# RF_Antenna.net
KiCad netlist of a schematic drawn in Altium Designer
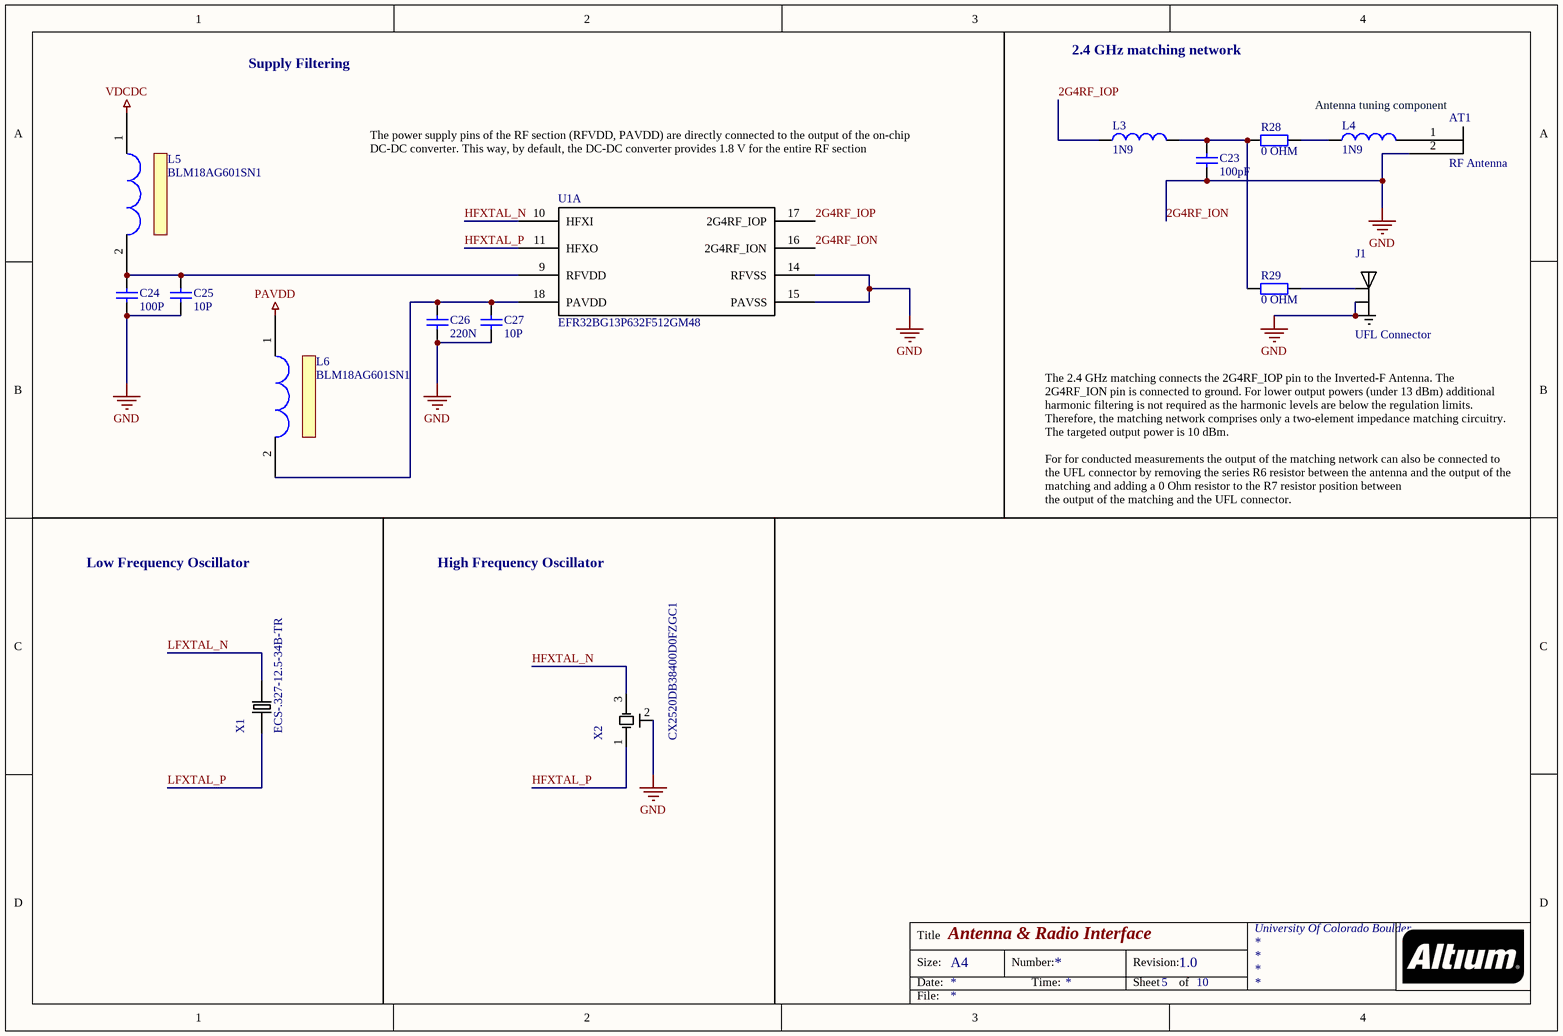
[diagram p0: RF_Antenna.SchDoc]

(export (version "E")
  (design (tool "Eeschema 10.0.6"))
  (components
    (comp (ref "AT1")
      (value "RF Antenna")
      (footprint "PCBComponent_1")
      (libsource (lib "Inverted_F") (part "RF Antenna"))
    )
    (comp (ref "C23")
      (value "100pF")
      (footprint "C1206")
      (description "CAP CER 1.5PF 50V C0G/NP0 0402")
      (fields
        (field (name "MANUFACTURER") "Murata Electronics")
        (field (name "MANUFACTURER PART NUMBER") "GJM1555C1H1R5WB01D")
      )
      (libsource (lib "Miscellaneous Devices") (part "Cap Semi"))
    )
    (comp (ref "C24")
      (value "100P")
      (footprint "1608[0603]")
      (description "CAP CER 100PF 16V X7R 0603")
      (fields
        (field (name "DIGIKEY PART NUMBER") "478-6207-1-ND")
        (field (name "MANUFACTURER") "AVX Corporation")
      )
      (libsource (lib "Miscellaneous Devices") (part "Cap"))
    )
    (comp (ref "C25")
      (value "10P")
      (footprint "1608[0603]")
      (description "CAP CER 10PF 50V C0G/NPO 0603")
      (fields (field (name "DIGI-KEY PART NUMBER") "311-1058-1-ND") (field (name "MANUFACTURER") "Yageo"))
      (libsource (lib "Miscellaneous Devices") (part "Cap"))
    )
    (comp (ref "C26")
      (value "220N")
      (footprint "1608[0603]")
      (description "Capacitor")
      (fields
        (field (name "DIGI-KEY PART NUMBER") "587-1249-1-ND")
        (field (name "MANUFACTURER") "Taiyo Yuden")
      )
      (libsource (lib "Miscellaneous Devices") (part "Cap"))
    )
    (comp (ref "C27")
      (value "10P")
      (footprint "1608[0603]")
      (description "CAP CER 10PF 50V C0G/NPO 0603")
      (fields (field (name "DIGI-KEY PART NUMBER") "311-1058-1-ND") (field (name "MANUFACTURER") "Yageo"))
      (libsource (lib "Miscellaneous Devices") (part "Cap"))
    )
    (comp (ref "J1")
      (value "UFL Connector")
      (footprint "*HRS_U.FL-R-SMT-1(10)")
      (description "U.FL Series 6 Ghz 50 Ohm Ultra-small SMT Coaxial Cable Receptacle")
      (fields
        (field (name "MOUSER PART NUMBER") "798-U.FL-R-SMT-110")
        (field (name "MANUFACTURER PART NUMBER") "U.FL-R-SMT-1(10)")
      )
      (libsource (lib "U.FL-R-SMT-1_10_") (part "U.FL-R-SMT-1(10)"))
    )
    (comp (ref "L3")
      (value "1N9")
      (footprint "0402-A")
      (description "FIXED IND 1.9NH 220MA 300 MOHM")
      (fields
        (field (name "MOUSER PART NUMBER") "81-LQP15MN1N9W02D")
        (field (name "MANUFACTURER") "Murata Electronics")
      )
      (libsource (lib "Miscellaneous Devices") (part "Inductor"))
    )
    (comp (ref "L4")
      (value "1N9")
      (footprint "0402-A")
      (description "FIXED IND 1.9NH 220MA 300 MOHM")
      (fields
        (field (name "MOUSER PART NUMBER") "81-LQP15MN1N9W02D")
        (field (name "MANUFACTURER") "Murata Electronics")
      )
      (libsource (lib "Miscellaneous Devices") (part "Inductor"))
    )
    (comp (ref "L5")
      (value "BLM18AG601SN1")
      (footprint "*CAPC0603X56N")
      (fields
        (field (name "MOUSER PART NUMBER") "81-BLM11A601S")
        (field (name "MANUFACTURER PART NUMBER") "BLM18AG601SN1D")
        (field (name "MANUFACTURER") "Murata Electronics")
      )
      (libsource (lib "LPEDT_Project_Library") (part "EMI Filter"))
    )
    (comp (ref "L6")
      (value "BLM18AG601SN1")
      (footprint "*CAPC0603X56N")
      (fields
        (field (name "MOUSER PART NUMBER") "81-BLM11A601S")
        (field (name "MANUFACTURER PART NUMBER") "BLM18AG601SN1D")
        (field (name "MANUFACTURER") "Murata Electronics")
      )
      (libsource (lib "LPEDT_Project_Library") (part "EMI Filter"))
    )
    (comp (ref "R28")
      (value "0 OHM")
      (footprint "1608[0603]")
      (description "RES SMD 0 OHM JUMPER 1/10W 0603")
      (fields (field (name "DIGI-KEY PART NUMBER") "311-0.0GRCT-ND") (field (name "MANUFACTURER") "Yageo"))
      (libsource (lib "Miscellaneous Devices") (part "Res2"))
    )
    (comp (ref "R29")
      (value "0 OHM")
      (footprint "1608[0603]")
      (description "RES SMD 0 OHM JUMPER 1/10W 0603")
      (fields (field (name "DIGI-KEY PART NUMBER") "311-0.0GRCT-ND") (field (name "MANUFACTURER") "Yageo"))
      (libsource (lib "Miscellaneous Devices") (part "Res2"))
    )
    (comp (ref "U1")
      (value "EFR32BG13P632F512GM48")
      (footprint "*QFN50P700X700X90-49N")
      (description "MCU")
      (fields
        (field (name "MANUFACTURER") "Silicon Labs")
        (field (name "MANUFACTURER PART NUMBER") "EFR32BG13P632F512GM48-BR")
      )
      (libsource (lib "EFR32BG13") (part "EFR32BG13"))
    )
    (comp (ref "X1")
      (value "ECS-.327-12.5-34B-TR")
      (footprint "*XTAL_ECS-.327-12.5-34B-TR")
      (description "Crystal 0.032768MHz Â±20ppm _Tol_ 12.5pF Flexural 70000Ohm 2-Pin Mini-SMD T/R")
      (fields (field (name "MOUSER PART NUMBER") "520-327-12.5-34B") (field (name "MANUFACTURER") "ECS"))
      (libsource (lib "ECS-.327-12.5-34B-TR") (part "ECS-.327-12.5-34B-TR"))
    )
    (comp (ref "X2")
      (value "CX2520DB38400D0FZGC1")
      (footprint "*OSCCC250X200X55N")
      (description "Crystal 38.4MHz 8pF 4-Pin SMD T/R")
      (fields
        (field (name "MOUSER PART NUMBER") "581-CX2520DB3D0FZGC1")
        (field (name "MANUFACTURER") "Kyocera Electronic Components")
      )
      (libsource (lib "CX2520DB38400D0FZGC1") (part "CX2520DB38400D0FZGC1"))
    )
  )
  (nets
    (net (code "1") (name "/2G4RF_IOP") (class "Default")
      (node (ref "L3") (pin "1") (pinfunction "1_1") (pintype "passive"))
      (node (ref "U1") (pin "17") (pinfunction "2G4RF_IOP_17") (pintype "passive"))
    )
    (net (code "2") (name "/HFXTAL_N") (class "Default")
      (node (ref "U1") (pin "10") (pinfunction "HFXI_10") (pintype "passive"))
      (node (ref "X2") (pin "3") (pinfunction "3_3") (pintype "passive"))
    )
    (net (code "3") (name "/HFXTAL_P") (class "Default")
      (node (ref "U1") (pin "11") (pinfunction "HFXO_11") (pintype "passive"))
      (node (ref "X2") (pin "1") (pinfunction "1_1") (pintype "passive"))
    )
    (net (code "4") (name "/LFXTAL_N") (class "Default")
      (node (ref "X1") (pin "2") (pinfunction "2_2") (pintype "passive"))
    )
    (net (code "5") (name "/LFXTAL_P") (class "Default")
      (node (ref "X1") (pin "1") (pinfunction "1_1") (pintype "passive"))
    )
    (net (code "6") (name "GND") (class "Default")
      (node (ref "AT1") (pin "2") (pintype "passive"))
      (node (ref "C23") (pin "1") (pinfunction "1_1") (pintype "passive"))
      (node (ref "C24") (pin "1") (pinfunction "1_1") (pintype "passive"))
      (node (ref "C25") (pin "1") (pinfunction "1_1") (pintype "passive"))
      (node (ref "C26") (pin "1") (pinfunction "1_1") (pintype "passive"))
      (node (ref "C27") (pin "1") (pinfunction "1_1") (pintype "passive"))
      (node (ref "J1") (pin "1") (pinfunction "GND_1") (pintype "passive"))
      (node (ref "J1") (pin "3") (pinfunction "GND_3") (pintype "passive"))
      (node (ref "U1") (pin "14") (pinfunction "RFVSS_14") (pintype "passive"))
      (node (ref "U1") (pin "15") (pinfunction "PAVSS_15") (pintype "passive"))
      (node (ref "U1") (pin "16") (pinfunction "2G4RF_ION_16") (pintype "passive"))
      (node (ref "X2") (pin "2") (pinfunction "GND_2") (pintype "passive"))
    )
    (net (code "7") (name "Net-(AT1-Pad1)") (class "Default")
      (node (ref "AT1") (pin "1") (pintype "passive"))
      (node (ref "L4") (pin "2") (pinfunction "2_2") (pintype "passive"))
    )
    (net (code "8") (name "Net-(C23-Pad2)") (class "Default")
      (node (ref "C23") (pin "2") (pinfunction "2_2") (pintype "passive"))
      (node (ref "L3") (pin "2") (pinfunction "2_2") (pintype "passive"))
      (node (ref "R28") (pin "1") (pinfunction "1_1") (pintype "passive"))
      (node (ref "R29") (pin "1") (pinfunction "1_1") (pintype "passive"))
    )
    (net (code "9") (name "Net-(J1-SIG)") (class "Default")
      (node (ref "J1") (pin "2") (pinfunction "SIG_2") (pintype "passive"))
      (node (ref "R29") (pin "2") (pinfunction "2_2") (pintype "passive"))
    )
    (net (code "10") (name "Net-(L4-Pad1)") (class "Default")
      (node (ref "L4") (pin "1") (pinfunction "1_1") (pintype "passive"))
      (node (ref "R28") (pin "2") (pinfunction "2_2") (pintype "passive"))
    )
    (net (code "11") (name "Net-(U1A-PAVDD)") (class "Default")
      (node (ref "C26") (pin "2") (pinfunction "2_2") (pintype "passive"))
      (node (ref "C27") (pin "2") (pinfunction "2_2") (pintype "passive"))
      (node (ref "L6") (pin "2") (pintype "passive"))
      (node (ref "U1") (pin "18") (pinfunction "PAVDD_18") (pintype "passive"))
    )
    (net (code "12") (name "Net-(U1A-RFVDD)") (class "Default")
      (node (ref "C24") (pin "2") (pinfunction "2_2") (pintype "passive"))
      (node (ref "C25") (pin "2") (pinfunction "2_2") (pintype "passive"))
      (node (ref "L5") (pin "2") (pintype "passive"))
      (node (ref "U1") (pin "9") (pinfunction "RFVDD_9") (pintype "passive"))
    )
    (net (code "13") (name "PAVDD") (class "Default") (node (ref "L6") (pin "1") (pintype "passive")))
    (net (code "14") (name "VDCDC") (class "Default") (node (ref "L5") (pin "1") (pintype "passive")))
  )
)
